# IR_PCB_Schematic.net
KiCad netlist of a schematic drawn in EAGLE
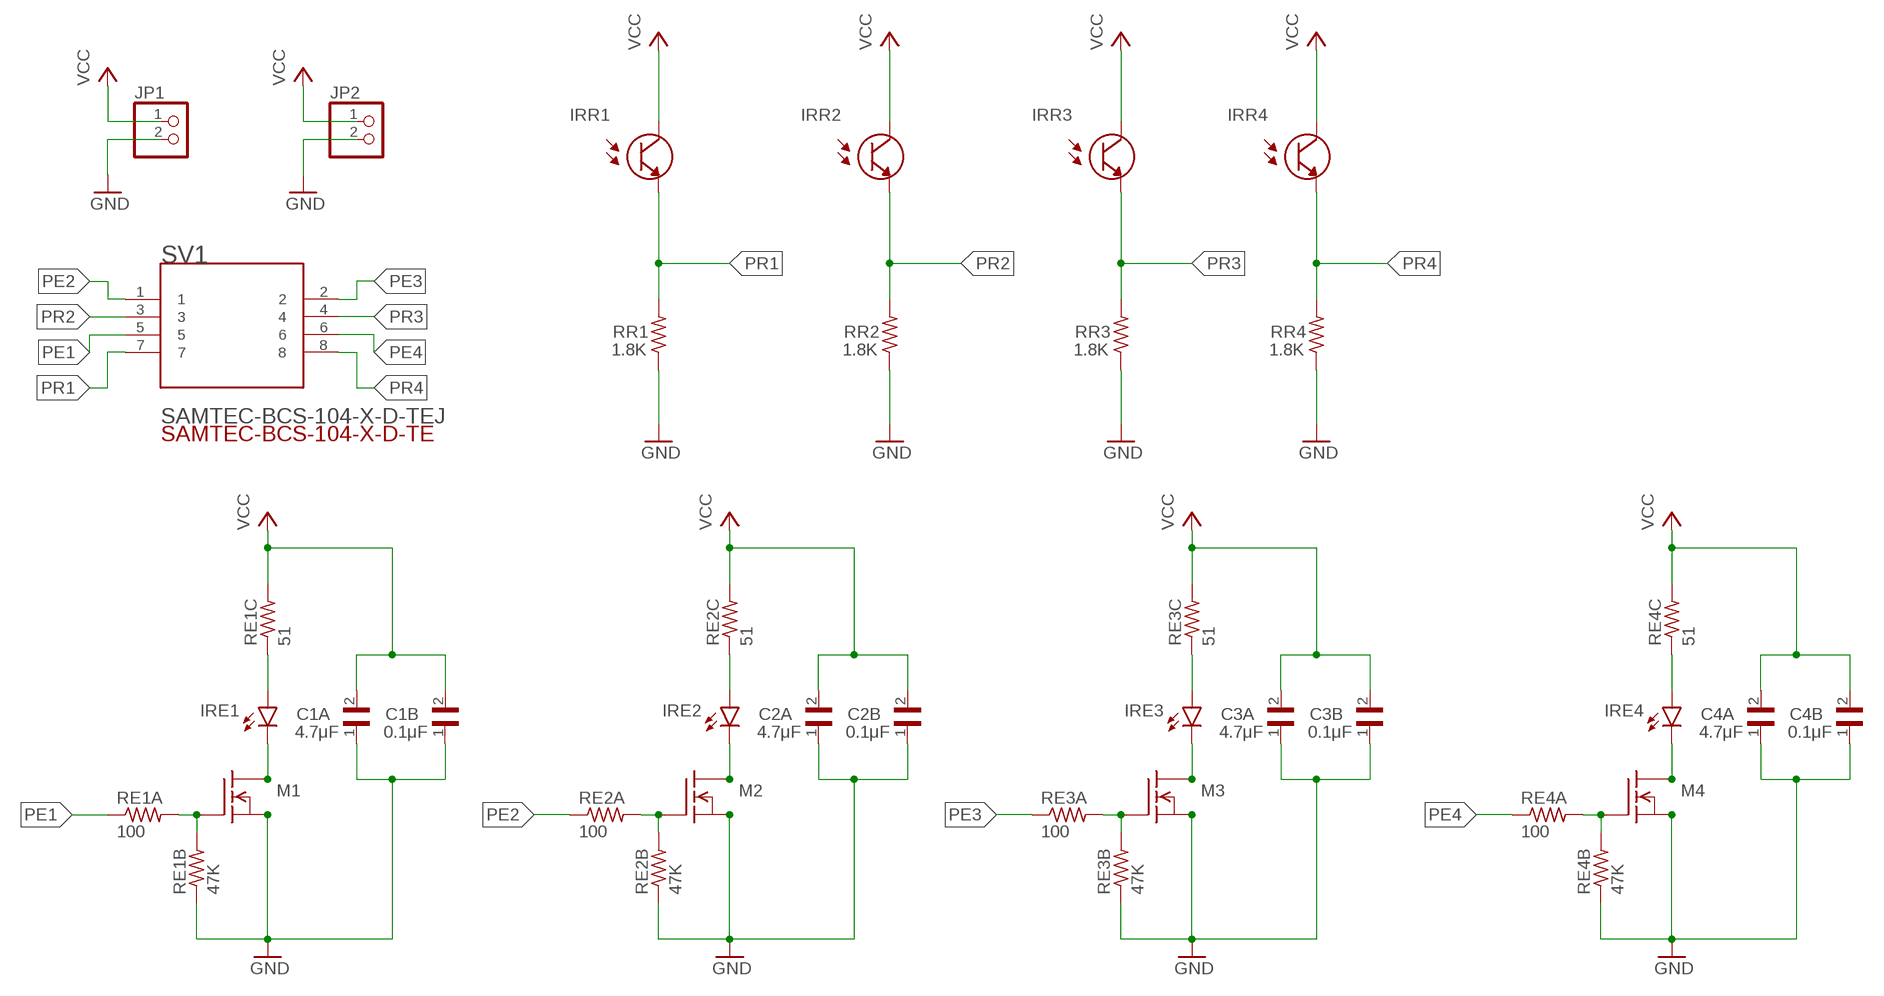
[diagram p0: schematic, sheet 1]

(export (version "E")
  (design (tool "Eeschema 10.0.6"))
  (components
    (comp (ref "C1A")
      (value "4.7μF")
      (footprint "eagle-import:CAPC2012X140N")
      (fields
        (field (name "DIGI-KEY_PART_NUMBER") "490-10516-1-ND")
        (field (name "MF") "Murata Electronics")
        (field (name "MP") "GRM21BR71A106KA73L")
      )
      (libsource (lib "eagle-import") (part "GRM21BR71A106KA73L"))
    )
    (comp (ref "C1B")
      (value "0.1μF")
      (footprint "eagle-import:CAPC2012X140N")
      (fields
        (field (name "DIGI-KEY_PART_NUMBER") "490-10516-1-ND")
        (field (name "MF") "Murata Electronics")
        (field (name "MP") "GRM21BR71A106KA73L")
      )
      (libsource (lib "eagle-import") (part "GRM21BR71A106KA73L"))
    )
    (comp (ref "C2A")
      (value "4.7μF")
      (footprint "eagle-import:CAPC2012X140N")
      (fields
        (field (name "DIGI-KEY_PART_NUMBER") "490-10516-1-ND")
        (field (name "MF") "Murata Electronics")
        (field (name "MP") "GRM21BR71A106KA73L")
      )
      (libsource (lib "eagle-import") (part "GRM21BR71A106KA73L"))
    )
    (comp (ref "C2B")
      (value "0.1μF")
      (footprint "eagle-import:CAPC2012X140N")
      (fields
        (field (name "DIGI-KEY_PART_NUMBER") "490-10516-1-ND")
        (field (name "MF") "Murata Electronics")
        (field (name "MP") "GRM21BR71A106KA73L")
      )
      (libsource (lib "eagle-import") (part "GRM21BR71A106KA73L"))
    )
    (comp (ref "C3A")
      (value "4.7μF")
      (footprint "eagle-import:CAPC2012X140N")
      (fields
        (field (name "DIGI-KEY_PART_NUMBER") "490-10516-1-ND")
        (field (name "MF") "Murata Electronics")
        (field (name "MP") "GRM21BR71A106KA73L")
      )
      (libsource (lib "eagle-import") (part "GRM21BR71A106KA73L"))
    )
    (comp (ref "C3B")
      (value "0.1μF")
      (footprint "eagle-import:CAPC2012X140N")
      (fields
        (field (name "DIGI-KEY_PART_NUMBER") "490-10516-1-ND")
        (field (name "MF") "Murata Electronics")
        (field (name "MP") "GRM21BR71A106KA73L")
      )
      (libsource (lib "eagle-import") (part "GRM21BR71A106KA73L"))
    )
    (comp (ref "C4A")
      (value "4.7μF")
      (footprint "eagle-import:CAPC2012X140N")
      (fields
        (field (name "DIGI-KEY_PART_NUMBER") "490-10516-1-ND")
        (field (name "MF") "Murata Electronics")
        (field (name "MP") "GRM21BR71A106KA73L")
      )
      (libsource (lib "eagle-import") (part "GRM21BR71A106KA73L"))
    )
    (comp (ref "C4B")
      (value "0.1μF")
      (footprint "eagle-import:CAPC2012X140N")
      (fields
        (field (name "DIGI-KEY_PART_NUMBER") "490-10516-1-ND")
        (field (name "MF") "Murata Electronics")
        (field (name "MP") "GRM21BR71A106KA73L")
      )
      (libsource (lib "eagle-import") (part "GRM21BR71A106KA73L"))
    )
    (comp (ref "IRE1")
      (value "LED5MM")
      (footprint "eagle-import:LED5MM")
      (libsource (lib "eagle-import") (part "LED5MM"))
    )
    (comp (ref "IRE2")
      (value "LED5MM")
      (footprint "eagle-import:LED5MM")
      (libsource (lib "eagle-import") (part "LED5MM"))
    )
    (comp (ref "IRE3")
      (value "LED5MM")
      (footprint "eagle-import:LED5MM")
      (libsource (lib "eagle-import") (part "LED5MM"))
    )
    (comp (ref "IRE4")
      (value "LED5MM")
      (footprint "eagle-import:LED5MM")
      (libsource (lib "eagle-import") (part "LED5MM"))
    )
    (comp (ref "IRR1")
      (value "SFH_313_FA-3/4")
      (footprint "eagle-import:XDCR_SFH_313_FA-3_4")
      (fields (field (name "MF") "OSRAM Opto") (field (name "MP") "SFH 313 FA-3/4"))
      (libsource (lib "eagle-import") (part "SFH_313_FA-3/4"))
    )
    (comp (ref "IRR2")
      (value "SFH_313_FA-3/4")
      (footprint "eagle-import:XDCR_SFH_313_FA-3_4")
      (fields (field (name "MF") "OSRAM Opto") (field (name "MP") "SFH 313 FA-3/4"))
      (libsource (lib "eagle-import") (part "SFH_313_FA-3/4"))
    )
    (comp (ref "IRR3")
      (value "SFH_313_FA-3/4")
      (footprint "eagle-import:XDCR_SFH_313_FA-3_4")
      (fields (field (name "MF") "OSRAM Opto") (field (name "MP") "SFH 313 FA-3/4"))
      (libsource (lib "eagle-import") (part "SFH_313_FA-3/4"))
    )
    (comp (ref "IRR4")
      (value "SFH_313_FA-3/4")
      (footprint "eagle-import:XDCR_SFH_313_FA-3_4")
      (fields (field (name "MF") "OSRAM Opto") (field (name "MP") "SFH 313 FA-3/4"))
      (libsource (lib "eagle-import") (part "SFH_313_FA-3/4"))
    )
    (comp (ref "JP1")
      (value "PINHD-1X2")
      (footprint "eagle-import:1X02")
      (libsource (lib "eagle-import") (part "PINHD-1X2"))
    )
    (comp (ref "JP2")
      (value "PINHD-1X2")
      (footprint "eagle-import:1X02")
      (libsource (lib "eagle-import") (part "PINHD-1X2"))
    )
    (comp (ref "M1")
      (value "2N7002")
      (footprint "eagle-import:SOT23")
      (fields (field (name "MF") "ON Semiconductor"))
      (libsource (lib "eagle-import") (part "2N7002"))
    )
    (comp (ref "M2")
      (value "2N7002")
      (footprint "eagle-import:SOT23")
      (fields (field (name "MF") "ON Semiconductor"))
      (libsource (lib "eagle-import") (part "2N7002"))
    )
    (comp (ref "M3")
      (value "2N7002")
      (footprint "eagle-import:SOT23")
      (fields (field (name "MF") "ON Semiconductor"))
      (libsource (lib "eagle-import") (part "2N7002"))
    )
    (comp (ref "M4")
      (value "2N7002")
      (footprint "eagle-import:SOT23")
      (fields (field (name "MF") "ON Semiconductor"))
      (libsource (lib "eagle-import") (part "2N7002"))
    )
    (comp (ref "RE1A")
      (value "100")
      (footprint "eagle-import:R0805")
      (libsource (lib "eagle-import") (part "R-US_R0805"))
    )
    (comp (ref "RE1B")
      (value "47K")
      (footprint "eagle-import:R0805")
      (libsource (lib "eagle-import") (part "R-US_R0805"))
    )
    (comp (ref "RE1C")
      (value "51")
      (footprint "eagle-import:R0805")
      (libsource (lib "eagle-import") (part "R-US_R0805"))
    )
    (comp (ref "RE2A")
      (value "100")
      (footprint "eagle-import:R0805")
      (libsource (lib "eagle-import") (part "R-US_R0805"))
    )
    (comp (ref "RE2B")
      (value "47K")
      (footprint "eagle-import:R0805")
      (libsource (lib "eagle-import") (part "R-US_R0805"))
    )
    (comp (ref "RE2C")
      (value "51")
      (footprint "eagle-import:R0805")
      (libsource (lib "eagle-import") (part "R-US_R0805"))
    )
    (comp (ref "RE3A")
      (value "100")
      (footprint "eagle-import:R0805")
      (libsource (lib "eagle-import") (part "R-US_R0805"))
    )
    (comp (ref "RE3B")
      (value "47K")
      (footprint "eagle-import:R0805")
      (libsource (lib "eagle-import") (part "R-US_R0805"))
    )
    (comp (ref "RE3C")
      (value "51")
      (footprint "eagle-import:R0805")
      (libsource (lib "eagle-import") (part "R-US_R0805"))
    )
    (comp (ref "RE4A")
      (value "100")
      (footprint "eagle-import:R0805")
      (libsource (lib "eagle-import") (part "R-US_R0805"))
    )
    (comp (ref "RE4B")
      (value "47K")
      (footprint "eagle-import:R0805")
      (libsource (lib "eagle-import") (part "R-US_R0805"))
    )
    (comp (ref "RE4C")
      (value "51")
      (footprint "eagle-import:R0805")
      (libsource (lib "eagle-import") (part "R-US_R0805"))
    )
    (comp (ref "RR1")
      (value "1.8K")
      (footprint "eagle-import:R0805")
      (libsource (lib "eagle-import") (part "R-US_R0805"))
    )
    (comp (ref "RR2")
      (value "1.8K")
      (footprint "eagle-import:R0805")
      (libsource (lib "eagle-import") (part "R-US_R0805"))
    )
    (comp (ref "RR3")
      (value "1.8K")
      (footprint "eagle-import:R0805")
      (libsource (lib "eagle-import") (part "R-US_R0805"))
    )
    (comp (ref "RR4")
      (value "1.8K")
      (footprint "eagle-import:R0805")
      (libsource (lib "eagle-import") (part "R-US_R0805"))
    )
    (comp (ref "SV1")
      (value "SAMTEC-BCS-104-X-D-TEJ")
      (footprint "eagle-import:SAMTEC-BCS-104-X-D-TE")
      (fields (field (name "MF") "Samtec") (field (name "MP") "BCS-104-T-D-TE"))
      (libsource (lib "eagle-import") (part "SAMTEC-BCS-104-X-D-TEJ"))
    )
  )
  (nets
    (net (code "1") (name "GND") (class "Default")
      (node (ref "C1A") (pin "1") (pinfunction "1_1") (pintype "passive"))
      (node (ref "C1B") (pin "1") (pinfunction "1_1") (pintype "passive"))
      (node (ref "C2A") (pin "1") (pinfunction "1_1") (pintype "passive"))
      (node (ref "C2B") (pin "1") (pinfunction "1_1") (pintype "passive"))
      (node (ref "C3A") (pin "1") (pinfunction "1_1") (pintype "passive"))
      (node (ref "C3B") (pin "1") (pinfunction "1_1") (pintype "passive"))
      (node (ref "C4A") (pin "1") (pinfunction "1_1") (pintype "passive"))
      (node (ref "C4B") (pin "1") (pinfunction "1_1") (pintype "passive"))
      (node (ref "JP1") (pin "2") (pinfunction "2_2") (pintype "passive"))
      (node (ref "JP2") (pin "2") (pinfunction "2_2") (pintype "passive"))
      (node (ref "M1") (pin "2") (pinfunction "S_2") (pintype "passive"))
      (node (ref "M2") (pin "2") (pinfunction "S_2") (pintype "passive"))
      (node (ref "M3") (pin "2") (pinfunction "S_2") (pintype "passive"))
      (node (ref "M4") (pin "2") (pinfunction "S_2") (pintype "passive"))
      (node (ref "RE1B") (pin "1") (pinfunction "1_1") (pintype "passive"))
      (node (ref "RE2B") (pin "1") (pinfunction "1_1") (pintype "passive"))
      (node (ref "RE3B") (pin "1") (pinfunction "1_1") (pintype "passive"))
      (node (ref "RE4B") (pin "1") (pinfunction "1_1") (pintype "passive"))
      (node (ref "RR1") (pin "1") (pinfunction "1_1") (pintype "passive"))
      (node (ref "RR2") (pin "1") (pinfunction "1_1") (pintype "passive"))
      (node (ref "RR3") (pin "1") (pinfunction "1_1") (pintype "passive"))
      (node (ref "RR4") (pin "1") (pinfunction "1_1") (pintype "passive"))
    )
    (net (code "2") (name "Net-(IRE1-C)") (class "Default")
      (node (ref "IRE1") (pin "K") (pinfunction "C_K") (pintype "passive"))
      (node (ref "M1") (pin "3") (pinfunction "D_3") (pintype "passive"))
    )
    (net (code "3") (name "Net-(IRE1-PadA)") (class "Default")
      (node (ref "IRE1") (pin "A") (pinfunction "A_A") (pintype "passive"))
      (node (ref "RE1C") (pin "1") (pinfunction "1_1") (pintype "passive"))
    )
    (net (code "4") (name "Net-(IRE2-C)") (class "Default")
      (node (ref "IRE2") (pin "K") (pinfunction "C_K") (pintype "passive"))
      (node (ref "M2") (pin "3") (pinfunction "D_3") (pintype "passive"))
    )
    (net (code "5") (name "Net-(IRE2-PadA)") (class "Default")
      (node (ref "IRE2") (pin "A") (pinfunction "A_A") (pintype "passive"))
      (node (ref "RE2C") (pin "1") (pinfunction "1_1") (pintype "passive"))
    )
    (net (code "6") (name "Net-(IRE3-C)") (class "Default")
      (node (ref "IRE3") (pin "K") (pinfunction "C_K") (pintype "passive"))
      (node (ref "M3") (pin "3") (pinfunction "D_3") (pintype "passive"))
    )
    (net (code "7") (name "Net-(IRE3-PadA)") (class "Default")
      (node (ref "IRE3") (pin "A") (pinfunction "A_A") (pintype "passive"))
      (node (ref "RE3C") (pin "1") (pinfunction "1_1") (pintype "passive"))
    )
    (net (code "8") (name "Net-(IRE4-C)") (class "Default")
      (node (ref "IRE4") (pin "K") (pinfunction "C_K") (pintype "passive"))
      (node (ref "M4") (pin "3") (pinfunction "D_3") (pintype "passive"))
    )
    (net (code "9") (name "Net-(IRE4-PadA)") (class "Default")
      (node (ref "IRE4") (pin "A") (pinfunction "A_A") (pintype "passive"))
      (node (ref "RE4C") (pin "1") (pinfunction "1_1") (pintype "passive"))
    )
    (net (code "10") (name "Net-(M1-G)") (class "Default")
      (node (ref "M1") (pin "1") (pinfunction "G_1") (pintype "passive"))
      (node (ref "RE1A") (pin "2") (pinfunction "2_2") (pintype "passive"))
      (node (ref "RE1B") (pin "2") (pinfunction "2_2") (pintype "passive"))
    )
    (net (code "11") (name "Net-(M2-G)") (class "Default")
      (node (ref "M2") (pin "1") (pinfunction "G_1") (pintype "passive"))
      (node (ref "RE2A") (pin "2") (pinfunction "2_2") (pintype "passive"))
      (node (ref "RE2B") (pin "2") (pinfunction "2_2") (pintype "passive"))
    )
    (net (code "12") (name "Net-(M3-G)") (class "Default")
      (node (ref "M3") (pin "1") (pinfunction "G_1") (pintype "passive"))
      (node (ref "RE3A") (pin "2") (pinfunction "2_2") (pintype "passive"))
      (node (ref "RE3B") (pin "2") (pinfunction "2_2") (pintype "passive"))
    )
    (net (code "13") (name "Net-(M4-G)") (class "Default")
      (node (ref "M4") (pin "1") (pinfunction "G_1") (pintype "passive"))
      (node (ref "RE4A") (pin "2") (pinfunction "2_2") (pintype "passive"))
      (node (ref "RE4B") (pin "2") (pinfunction "2_2") (pintype "passive"))
    )
    (net (code "14") (name "PE1") (class "Default")
      (node (ref "RE1A") (pin "1") (pinfunction "1_1") (pintype "passive"))
      (node (ref "SV1") (pin "5") (pinfunction "5_5") (pintype "passive"))
    )
    (net (code "15") (name "PE2") (class "Default")
      (node (ref "RE2A") (pin "1") (pinfunction "1_1") (pintype "passive"))
      (node (ref "SV1") (pin "1") (pinfunction "1_1") (pintype "passive"))
    )
    (net (code "16") (name "PE3") (class "Default")
      (node (ref "RE3A") (pin "1") (pinfunction "1_1") (pintype "passive"))
      (node (ref "SV1") (pin "2") (pinfunction "2_2") (pintype "passive"))
    )
    (net (code "17") (name "PE4") (class "Default")
      (node (ref "RE4A") (pin "1") (pinfunction "1_1") (pintype "passive"))
      (node (ref "SV1") (pin "6") (pinfunction "6_6") (pintype "passive"))
    )
    (net (code "18") (name "PR1") (class "Default")
      (node (ref "IRR1") (pin "1") (pinfunction "E_1") (pintype "passive"))
      (node (ref "RR1") (pin "2") (pinfunction "2_2") (pintype "passive"))
      (node (ref "SV1") (pin "7") (pinfunction "7_7") (pintype "passive"))
    )
    (net (code "19") (name "PR2") (class "Default")
      (node (ref "IRR2") (pin "1") (pinfunction "E_1") (pintype "passive"))
      (node (ref "RR2") (pin "2") (pinfunction "2_2") (pintype "passive"))
      (node (ref "SV1") (pin "3") (pinfunction "3_3") (pintype "passive"))
    )
    (net (code "20") (name "PR3") (class "Default")
      (node (ref "IRR3") (pin "1") (pinfunction "E_1") (pintype "passive"))
      (node (ref "RR3") (pin "2") (pinfunction "2_2") (pintype "passive"))
      (node (ref "SV1") (pin "4") (pinfunction "4_4") (pintype "passive"))
    )
    (net (code "21") (name "PR4") (class "Default")
      (node (ref "IRR4") (pin "1") (pinfunction "E_1") (pintype "passive"))
      (node (ref "RR4") (pin "2") (pinfunction "2_2") (pintype "passive"))
      (node (ref "SV1") (pin "8") (pinfunction "8_8") (pintype "passive"))
    )
    (net (code "22") (name "VCC") (class "Default")
      (node (ref "C1A") (pin "2") (pinfunction "2_2") (pintype "passive"))
      (node (ref "C1B") (pin "2") (pinfunction "2_2") (pintype "passive"))
      (node (ref "C2A") (pin "2") (pinfunction "2_2") (pintype "passive"))
      (node (ref "C2B") (pin "2") (pinfunction "2_2") (pintype "passive"))
      (node (ref "C3A") (pin "2") (pinfunction "2_2") (pintype "passive"))
      (node (ref "C3B") (pin "2") (pinfunction "2_2") (pintype "passive"))
      (node (ref "C4A") (pin "2") (pinfunction "2_2") (pintype "passive"))
      (node (ref "C4B") (pin "2") (pinfunction "2_2") (pintype "passive"))
      (node (ref "IRR1") (pin "2") (pinfunction "C_2") (pintype "passive"))
      (node (ref "IRR2") (pin "2") (pinfunction "C_2") (pintype "passive"))
      (node (ref "IRR3") (pin "2") (pinfunction "C_2") (pintype "passive"))
      (node (ref "IRR4") (pin "2") (pinfunction "C_2") (pintype "passive"))
      (node (ref "JP1") (pin "1") (pinfunction "1_1") (pintype "passive"))
      (node (ref "JP2") (pin "1") (pinfunction "1_1") (pintype "passive"))
      (node (ref "RE1C") (pin "2") (pinfunction "2_2") (pintype "passive"))
      (node (ref "RE2C") (pin "2") (pinfunction "2_2") (pintype "passive"))
      (node (ref "RE3C") (pin "2") (pinfunction "2_2") (pintype "passive"))
      (node (ref "RE4C") (pin "2") (pinfunction "2_2") (pintype "passive"))
    )
  )
)
